# FM_TX.net
KiCad netlist of a schematic drawn in Altium Designer
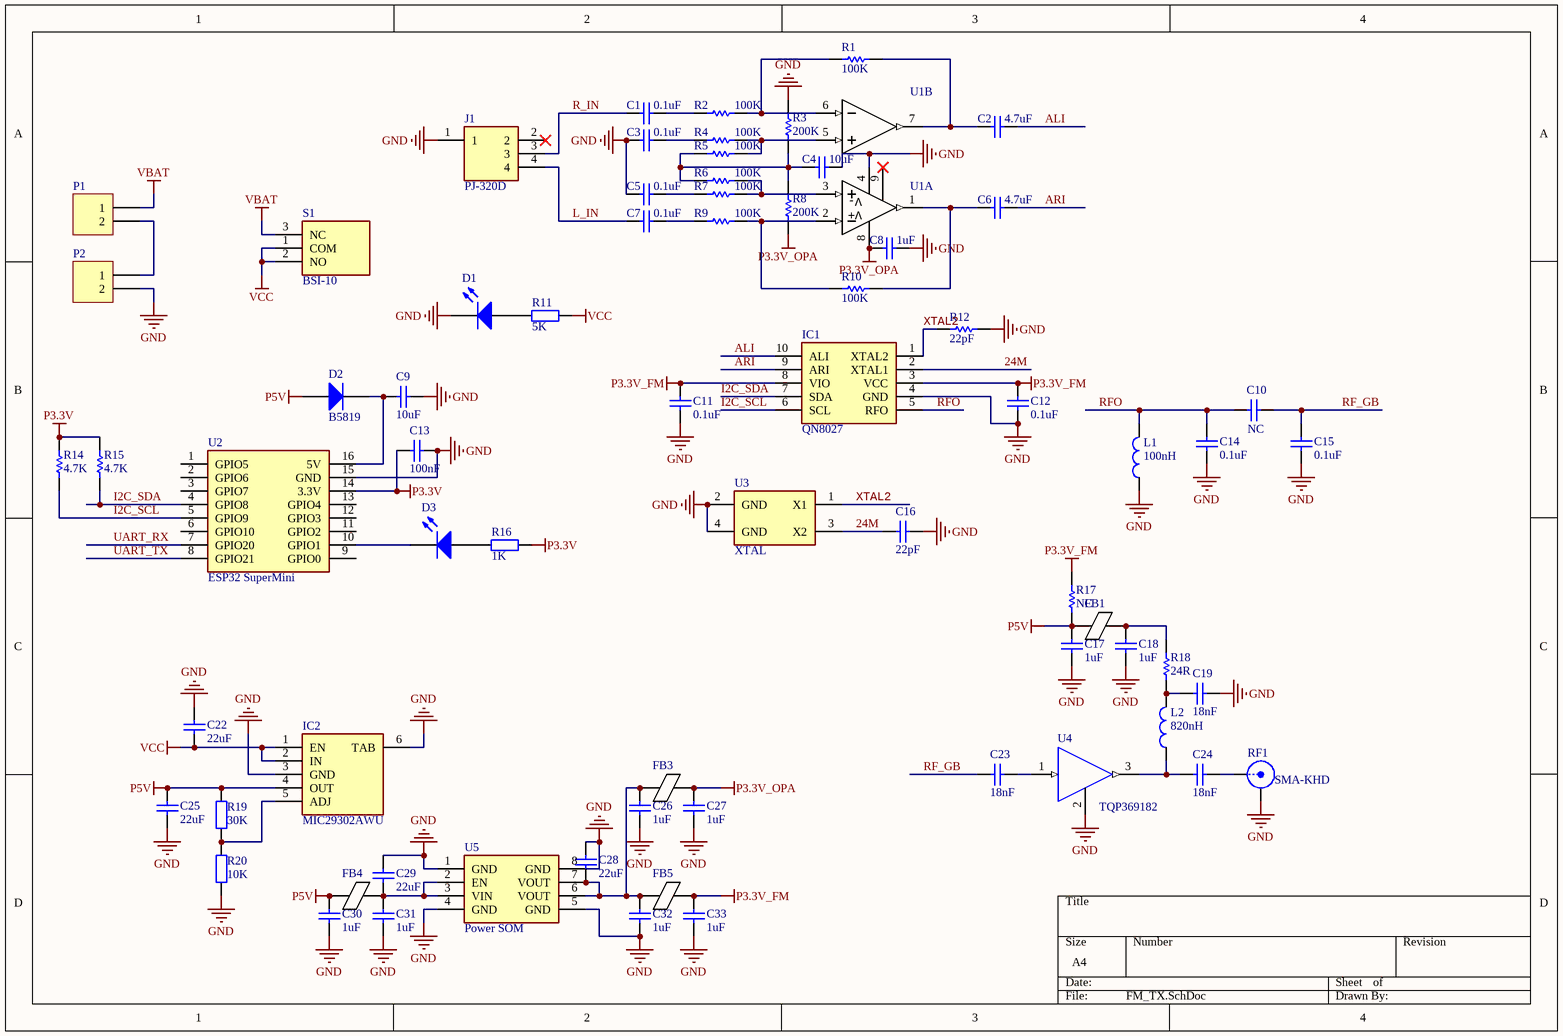
[diagram p0: FM_TX.SchDoc]

(export (version "E")
  (design (tool "Eeschema 10.0.6"))
  (components
    (comp (ref "C1")
      (value "0.1uF")
      (footprint "0603_C")
      (description "Capacitor")
      (fields (field (name "PUBLISHER") "Altium Limited"))
      (libsource (lib "My Footprint") (part "CAP"))
    )
    (comp (ref "C2")
      (value "4.7uF")
      (footprint "0603_C")
      (description "Capacitor")
      (fields (field (name "PUBLISHER") "Altium Limited"))
      (libsource (lib "My Footprint") (part "CAP"))
    )
    (comp (ref "C3")
      (value "0.1uF")
      (footprint "0603_C")
      (description "Capacitor")
      (fields (field (name "PUBLISHER") "Altium Limited"))
      (libsource (lib "My Footprint") (part "CAP"))
    )
    (comp (ref "C4")
      (value "10uF")
      (footprint "0603_C")
      (description "Capacitor")
      (fields (field (name "PUBLISHER") "Altium Limited"))
      (libsource (lib "My Footprint") (part "CAP"))
    )
    (comp (ref "C5")
      (value "0.1uF")
      (footprint "0603_C")
      (description "Capacitor")
      (fields (field (name "PUBLISHER") "Altium Limited"))
      (libsource (lib "My Footprint") (part "CAP"))
    )
    (comp (ref "C6")
      (value "4.7uF")
      (footprint "0603_C")
      (description "Capacitor")
      (fields (field (name "PUBLISHER") "Altium Limited"))
      (libsource (lib "My Footprint") (part "CAP"))
    )
    (comp (ref "C7")
      (value "0.1uF")
      (footprint "0603_C")
      (description "Capacitor")
      (fields (field (name "PUBLISHER") "Altium Limited"))
      (libsource (lib "My Footprint") (part "CAP"))
    )
    (comp (ref "C8")
      (value "1uF")
      (footprint "0603_C")
      (description "Capacitor")
      (fields (field (name "PUBLISHER") "Altium Limited"))
      (libsource (lib "My Footprint") (part "CAP"))
    )
    (comp (ref "C9")
      (value "10uF")
      (footprint "C1210")
      (description "Capacitor")
      (fields (field (name "Comment") "Cap") (field (name "PUBLISHER") "Altium Limited"))
      (libsource (lib "RegenovoPcbLib") (part "Cap"))
    )
    (comp (ref "C10")
      (value "NC")
      (footprint "0603_C")
      (description "Capacitor")
      (fields (field (name "PUBLISHER") "Altium Limited"))
      (libsource (lib "My Footprint") (part "CAP"))
    )
    (comp (ref "C11")
      (value "0.1uF")
      (footprint "0603_C")
      (description "Capacitor")
      (fields (field (name "PUBLISHER") "Altium Limited"))
      (libsource (lib "My Footprint") (part "CAP"))
    )
    (comp (ref "C12")
      (value "0.1uF")
      (footprint "0603_C")
      (description "Capacitor")
      (fields (field (name "PUBLISHER") "Altium Limited"))
      (libsource (lib "My Footprint") (part "CAP"))
    )
    (comp (ref "C13")
      (value "100nF")
      (footprint "C0603")
      (description "Capacitor")
      (fields (field (name "Comment") "Cap") (field (name "PUBLISHER") "Altium Limited"))
      (libsource (lib "RegenovoPcbLib") (part "Cap"))
    )
    (comp (ref "C14")
      (value "0.1uF")
      (footprint "0603_C")
      (description "Capacitor")
      (fields (field (name "PUBLISHER") "Altium Limited"))
      (libsource (lib "My Footprint") (part "CAP"))
    )
    (comp (ref "C15")
      (value "0.1uF")
      (footprint "0603_C")
      (description "Capacitor")
      (fields (field (name "PUBLISHER") "Altium Limited"))
      (libsource (lib "My Footprint") (part "CAP"))
    )
    (comp (ref "C16")
      (value "22pF")
      (footprint "0603_C")
      (description "Capacitor")
      (fields (field (name "PUBLISHER") "Altium Limited"))
      (libsource (lib "My Footprint") (part "CAP"))
    )
    (comp (ref "C17")
      (value "1uF")
      (footprint "0603_C")
      (description "Capacitor")
      (fields (field (name "PUBLISHER") "Altium Limited"))
      (libsource (lib "My Footprint") (part "CAP"))
    )
    (comp (ref "C18")
      (value "1uF")
      (footprint "0603_C")
      (description "Capacitor")
      (fields (field (name "PUBLISHER") "Altium Limited"))
      (libsource (lib "My Footprint") (part "CAP"))
    )
    (comp (ref "C19")
      (value "18nF")
      (footprint "0603_C")
      (description "Capacitor")
      (fields (field (name "PUBLISHER") "Altium Limited"))
      (libsource (lib "My Footprint") (part "CAP"))
    )
    (comp (ref "C22")
      (value "22uF")
      (footprint "C1210")
      (description "Capacitor")
      (fields (field (name "Comment") "Cap") (field (name "PUBLISHER") "Altium Limited"))
      (libsource (lib "RegenovoPcbLib") (part "Cap"))
    )
    (comp (ref "C23")
      (value "18nF")
      (footprint "0603_C")
      (description "Capacitor")
      (fields (field (name "PUBLISHER") "Altium Limited"))
      (libsource (lib "My Footprint") (part "CAP"))
    )
    (comp (ref "C24")
      (value "18nF")
      (footprint "0603_C")
      (description "Capacitor")
      (fields (field (name "PUBLISHER") "Altium Limited"))
      (libsource (lib "My Footprint") (part "CAP"))
    )
    (comp (ref "C25")
      (value "22uF")
      (footprint "C1210")
      (description "Capacitor")
      (fields (field (name "Comment") "Cap") (field (name "PUBLISHER") "Altium Limited"))
      (libsource (lib "RegenovoPcbLib") (part "Cap"))
    )
    (comp (ref "C26")
      (value "1uF")
      (footprint "0603_C")
      (description "Capacitor")
      (fields (field (name "PUBLISHER") "Altium Limited"))
      (libsource (lib "My Footprint") (part "CAP"))
    )
    (comp (ref "C27")
      (value "1uF")
      (footprint "0603_C")
      (description "Capacitor")
      (fields (field (name "PUBLISHER") "Altium Limited"))
      (libsource (lib "My Footprint") (part "CAP"))
    )
    (comp (ref "C28")
      (value "22uF")
      (footprint "C1210")
      (description "Capacitor")
      (fields (field (name "Comment") "Cap") (field (name "PUBLISHER") "Altium Limited"))
      (libsource (lib "RegenovoPcbLib") (part "Cap"))
    )
    (comp (ref "C29")
      (value "22uF")
      (footprint "C1210")
      (description "Capacitor")
      (fields (field (name "Comment") "Cap") (field (name "PUBLISHER") "Altium Limited"))
      (libsource (lib "RegenovoPcbLib") (part "Cap"))
    )
    (comp (ref "C30")
      (value "1uF")
      (footprint "0603_C")
      (description "Capacitor")
      (fields (field (name "PUBLISHER") "Altium Limited"))
      (libsource (lib "My Footprint") (part "CAP"))
    )
    (comp (ref "C31")
      (value "1uF")
      (footprint "0603_C")
      (description "Capacitor")
      (fields (field (name "PUBLISHER") "Altium Limited"))
      (libsource (lib "My Footprint") (part "CAP"))
    )
    (comp (ref "C32")
      (value "1uF")
      (footprint "0603_C")
      (description "Capacitor")
      (fields (field (name "PUBLISHER") "Altium Limited"))
      (libsource (lib "My Footprint") (part "CAP"))
    )
    (comp (ref "C33")
      (value "1uF")
      (footprint "0603_C")
      (description "Capacitor")
      (fields (field (name "PUBLISHER") "Altium Limited"))
      (libsource (lib "My Footprint") (part "CAP"))
    )
    (comp (ref "D1")
      (value "LED")
      (footprint "LED 0603B")
      (description "Typical RED, GREEN, YELLOW, AMBER GaAs LED")
      (fields (field (name "PUBLISHER") "Altium Limited"))
      (libsource (lib "RegenovoPcbLib") (part "LED"))
    )
    (comp (ref "D2")
      (value "B5819")
      (footprint "SOD123")
      (libsource (lib "RegenovoPcbLib") (part "Diode B5819"))
    )
    (comp (ref "D3")
      (value "LED")
      (footprint "LED 0603B")
      (description "Typical RED, GREEN, YELLOW, AMBER GaAs LED")
      (fields (field (name "PUBLISHER") "Altium Limited"))
      (libsource (lib "RegenovoPcbLib") (part "LED"))
    )
    (comp (ref "FB1")
      (value "600Ω @ 100MHz")
      (footprint "0603")
      (description "磁珠 600Ω @ 100MHz")
      (libsource (lib "My Footprint") (part "FB"))
    )
    (comp (ref "FB3")
      (value "600Ω @ 100MHz")
      (footprint "0603")
      (description "磁珠 600Ω @ 100MHz")
      (libsource (lib "My Footprint") (part "FB"))
    )
    (comp (ref "FB4")
      (value "600Ω @ 100MHz")
      (footprint "0603")
      (description "磁珠 600Ω @ 100MHz")
      (libsource (lib "My Footprint") (part "FB"))
    )
    (comp (ref "FB5")
      (value "600Ω @ 100MHz")
      (footprint "0603")
      (description "磁珠 600Ω @ 100MHz")
      (libsource (lib "My Footprint") (part "FB"))
    )
    (comp (ref "IC1")
      (value "QN8027")
      (footprint "SOP50P490X110-10N")
      (description "Integrated Circuit")
      (libsource (lib "SamacSys") (part "QN8027"))
    )
    (comp (ref "IC2")
      (value "MIC29302AWU")
      (footprint "KTT0005B")
      (description "Integrated Circuit")
      (fields (field (name "MOUSER PART NUMBER") "998-MIC29302AWU"))
      (libsource (lib "SamacSys") (part "MIC29302AWU"))
    )
    (comp (ref "J1")
      (value "PJ-320D")
      (footprint "PJ320D")
      (description "Connector")
      (libsource (lib "SamacSys") (part "PJ-320D"))
    )
    (comp (ref "L1") (value "100nH") (footprint "0805") (libsource (lib "My Footprint") (part "Inductor")))
    (comp (ref "L2") (value "820nH") (footprint "0805") (libsource (lib "My Footprint") (part "Inductor")))
    (comp (ref "P1")
      (value "Header 2")
      (footprint "XH2.54-WI-2P")
      (description "Header, 2-Pin")
      (fields (field (name "PUBLISHER") "Altium Limited"))
      (libsource (lib "RegenovoPcbLib") (part "Header 2"))
    )
    (comp (ref "P2")
      (value "Header 2")
      (footprint "XH2.54-WI-2P")
      (description "Header, 2-Pin")
      (fields (field (name "PUBLISHER") "Altium Limited"))
      (libsource (lib "RegenovoPcbLib") (part "Header 2"))
    )
    (comp (ref "R1")
      (value "100K")
      (footprint "0603_R")
      (description "Resistor")
      (fields (field (name "PUBLISHER") "Altium Limited"))
      (libsource (lib "My Footprint") (part "RES"))
    )
    (comp (ref "R2")
      (value "100K")
      (footprint "0603_R")
      (description "Resistor")
      (fields (field (name "PUBLISHER") "Altium Limited"))
      (libsource (lib "My Footprint") (part "RES"))
    )
    (comp (ref "R3")
      (value "200K")
      (footprint "0603_R")
      (description "Resistor")
      (fields (field (name "PUBLISHER") "Altium Limited"))
      (libsource (lib "My Footprint") (part "RES"))
    )
    (comp (ref "R4")
      (value "100K")
      (footprint "0603_R")
      (description "Resistor")
      (fields (field (name "PUBLISHER") "Altium Limited"))
      (libsource (lib "My Footprint") (part "RES"))
    )
    (comp (ref "R5")
      (value "100K")
      (footprint "0603_R")
      (description "Resistor")
      (fields (field (name "PUBLISHER") "Altium Limited"))
      (libsource (lib "My Footprint") (part "RES"))
    )
    (comp (ref "R6")
      (value "100K")
      (footprint "0603_R")
      (description "Resistor")
      (fields (field (name "PUBLISHER") "Altium Limited"))
      (libsource (lib "My Footprint") (part "RES"))
    )
    (comp (ref "R7")
      (value "100K")
      (footprint "0603_R")
      (description "Resistor")
      (fields (field (name "PUBLISHER") "Altium Limited"))
      (libsource (lib "My Footprint") (part "RES"))
    )
    (comp (ref "R8")
      (value "200K")
      (footprint "0603_R")
      (description "Resistor")
      (fields (field (name "PUBLISHER") "Altium Limited"))
      (libsource (lib "My Footprint") (part "RES"))
    )
    (comp (ref "R9")
      (value "100K")
      (footprint "0603_R")
      (description "Resistor")
      (fields (field (name "PUBLISHER") "Altium Limited"))
      (libsource (lib "My Footprint") (part "RES"))
    )
    (comp (ref "R10")
      (value "100K")
      (footprint "0603_R")
      (description "Resistor")
      (fields (field (name "PUBLISHER") "Altium Limited"))
      (libsource (lib "My Footprint") (part "RES"))
    )
    (comp (ref "R11")
      (value "5K")
      (footprint "R0603")
      (description "Resistor")
      (fields (field (name "Comment") "Res") (field (name "PUBLISHER") "Altium Limited"))
      (libsource (lib "") (part "Res_1"))
    )
    (comp (ref "R12")
      (value "22pF")
      (footprint "0603_R")
      (description "Resistor")
      (fields (field (name "PUBLISHER") "Altium Limited"))
      (libsource (lib "My Footprint") (part "RES"))
    )
    (comp (ref "R14")
      (value "4.7K")
      (footprint "0603_R")
      (description "Resistor")
      (fields (field (name "PUBLISHER") "Altium Limited"))
      (libsource (lib "My Footprint") (part "RES"))
    )
    (comp (ref "R15")
      (value "4.7K")
      (footprint "0603_R")
      (description "Resistor")
      (fields (field (name "PUBLISHER") "Altium Limited"))
      (libsource (lib "My Footprint") (part "RES"))
    )
    (comp (ref "R16")
      (value "1K")
      (footprint "R0603")
      (description "Resistor")
      (fields (field (name "Comment") "Res") (field (name "PUBLISHER") "Altium Limited"))
      (libsource (lib "") (part "Res_1"))
    )
    (comp (ref "R17")
      (value "NC")
      (footprint "0603_R")
      (description "Resistor")
      (fields (field (name "PUBLISHER") "Altium Limited"))
      (libsource (lib "My Footprint") (part "RES"))
    )
    (comp (ref "R18")
      (value "24R")
      (footprint "0603_R")
      (description "Resistor")
      (fields (field (name "PUBLISHER") "Altium Limited"))
      (libsource (lib "My Footprint") (part "RES"))
    )
    (comp (ref "R19")
      (value "30K")
      (footprint "R0603")
      (description "Resistor")
      (fields (field (name "Comment") "Res") (field (name "PUBLISHER") "Altium Limited"))
      (libsource (lib "RegenovoPcbLib") (part "Res"))
    )
    (comp (ref "R20")
      (value "10K")
      (footprint "R0603")
      (description "Resistor")
      (fields (field (name "Comment") "Res") (field (name "PUBLISHER") "Altium Limited"))
      (libsource (lib "RegenovoPcbLib") (part "Res"))
    )
    (comp (ref "RF1") (value "SMA-KHD") (footprint "SMA-2") (libsource (lib "My Footprint") (part "SMA_KHD")))
    (comp (ref "S1")
      (value "BSI-10")
      (footprint "BSI10")
      (description "Switch")
      (libsource (lib "SamacSys") (part "BSI-10"))
    )
    (comp (ref "U1")
      (value "OPA2211AIDRGR")
      (footprint "SOIC-8")
      (description "Imported")
      (fields
        (field (name "MANUFACTURER") "Texas Instruments")
        (field (name "GENERIC_PART_NUMBER") "OPA2365")
      )
      (libsource (lib "SamacSys") (part "OPA2211"))
    )
    (comp (ref "U2")
      (value "ESP32 SuperMini")
      (footprint "ESP32C3_MINI")
      (libsource (lib "ESP32C3") (part "ESP32 SuperMini"))
    )
    (comp (ref "U3")
      (value "XTAL")
      (footprint "OSC_KH3225_4P")
      (libsource (lib "My Footprint") (part "XTAL_SMT"))
    )
    (comp (ref "U4") (value "TQP369182") (footprint "SOT-89") (libsource (lib "My Footprint") (part "LNA")))
    (comp (ref "U5")
      (value "Power SOM")
      (footprint "7A8300")
      (libsource (lib "power_module") (part "TPS7A8300"))
    )
  )
  (nets
    (net (code "1") (name "/24M") (class "Default")
      (node (ref "C16") (pin "2") (pinfunction "2_2") (pintype "passive"))
      (node (ref "IC1") (pin "2") (pinfunction "XTAL1_2") (pintype "passive"))
      (node (ref "U3") (pin "3") (pinfunction "X2_3") (pintype "passive"))
    )
    (net (code "2") (name "/ALI") (class "Default")
      (node (ref "C2") (pin "2") (pinfunction "2_2") (pintype "passive"))
      (node (ref "IC1") (pin "10") (pinfunction "ALI_10") (pintype "passive"))
    )
    (net (code "3") (name "/ARI") (class "Default")
      (node (ref "C6") (pin "2") (pinfunction "2_2") (pintype "passive"))
      (node (ref "IC1") (pin "9") (pinfunction "ARI_9") (pintype "passive"))
    )
    (net (code "4") (name "/I2C_SCL") (class "Default")
      (node (ref "IC1") (pin "6") (pinfunction "SCL_6") (pintype "passive"))
      (node (ref "R14") (pin "1") (pinfunction "1_1") (pintype "passive"))
      (node (ref "U2") (pin "5") (pinfunction "GPIO9_5") (pintype "passive"))
    )
    (net (code "5") (name "/I2C_SDA") (class "Default")
      (node (ref "IC1") (pin "7") (pinfunction "SDA_7") (pintype "passive"))
      (node (ref "R15") (pin "1") (pinfunction "1_1") (pintype "passive"))
      (node (ref "U2") (pin "4") (pinfunction "GPIO8_4") (pintype "passive"))
    )
    (net (code "6") (name "/L_IN") (class "Default")
      (node (ref "C7") (pin "1") (pinfunction "1_1") (pintype "passive"))
      (node (ref "J1") (pin "4") (pinfunction "4_4") (pintype "passive"))
    )
    (net (code "7") (name "/RFO") (class "Default")
      (node (ref "C10") (pin "2") (pinfunction "2_2") (pintype "passive"))
      (node (ref "C14") (pin "2") (pinfunction "2_2") (pintype "passive"))
      (node (ref "IC1") (pin "5") (pinfunction "RFO_5") (pintype "passive"))
      (node (ref "L1") (pin "2") (pinfunction "2_2") (pintype "passive"))
    )
    (net (code "8") (name "/RF_GB") (class "Default")
      (node (ref "C10") (pin "1") (pinfunction "1_1") (pintype "passive"))
      (node (ref "C15") (pin "2") (pinfunction "2_2") (pintype "passive"))
      (node (ref "C23") (pin "1") (pinfunction "1_1") (pintype "passive"))
    )
    (net (code "9") (name "/R_IN") (class "Default")
      (node (ref "C1") (pin "1") (pinfunction "1_1") (pintype "passive"))
      (node (ref "J1") (pin "3") (pinfunction "3_3") (pintype "passive"))
    )
    (net (code "10") (name "/UART_RX") (class "Default")
      (node (ref "U2") (pin "7") (pinfunction "GPIO20_7") (pintype "passive"))
    )
    (net (code "11") (name "/UART_TX") (class "Default")
      (node (ref "U2") (pin "8") (pinfunction "GPIO21_8") (pintype "passive"))
    )
    (net (code "12") (name "/XTAL2") (class "Default")
      (node (ref "IC1") (pin "1") (pinfunction "XTAL2_1") (pintype "passive"))
      (node (ref "R12") (pin "1") (pinfunction "1_1") (pintype "passive"))
      (node (ref "U3") (pin "1") (pinfunction "X1_1") (pintype "passive"))
    )
    (net (code "13") (name "GND") (class "Default")
      (node (ref "C11") (pin "1") (pinfunction "1_1") (pintype "passive"))
      (node (ref "C12") (pin "1") (pinfunction "1_1") (pintype "passive"))
      (node (ref "C13") (pin "2") (pinfunction "2_2") (pintype "passive"))
      (node (ref "C14") (pin "1") (pinfunction "1_1") (pintype "passive"))
      (node (ref "C15") (pin "1") (pinfunction "1_1") (pintype "passive"))
      (node (ref "C16") (pin "1") (pinfunction "1_1") (pintype "passive"))
      (node (ref "C17") (pin "1") (pinfunction "1_1") (pintype "passive"))
      (node (ref "C18") (pin "1") (pinfunction "1_1") (pintype "passive"))
      (node (ref "C19") (pin "2") (pinfunction "2_2") (pintype "passive"))
      (node (ref "C22") (pin "1") (pinfunction "1_1") (pintype "passive"))
      (node (ref "C25") (pin "1") (pinfunction "1_1") (pintype "passive"))
      (node (ref "C26") (pin "1") (pinfunction "1_1") (pintype "passive"))
      (node (ref "C27") (pin "1") (pinfunction "1_1") (pintype "passive"))
      (node (ref "C28") (pin "1") (pinfunction "1_1") (pintype "passive"))
      (node (ref "C29") (pin "2") (pinfunction "2_2") (pintype "passive"))
      (node (ref "C3") (pin "1") (pinfunction "1_1") (pintype "passive"))
      (node (ref "C30") (pin "1") (pinfunction "1_1") (pintype "passive"))
      (node (ref "C31") (pin "1") (pinfunction "1_1") (pintype "passive"))
      (node (ref "C32") (pin "1") (pinfunction "1_1") (pintype "passive"))
      (node (ref "C33") (pin "1") (pinfunction "1_1") (pintype "passive"))
      (node (ref "C4") (pin "2") (pinfunction "2_2") (pintype "passive"))
      (node (ref "C5") (pin "1") (pinfunction "1_1") (pintype "passive"))
      (node (ref "C8") (pin "2") (pinfunction "2_2") (pintype "passive"))
      (node (ref "C9") (pin "1") (pinfunction "1_1") (pintype "passive"))
      (node (ref "D1") (pin "2") (pinfunction "K_2") (pintype "passive"))
      (node (ref "IC1") (pin "4") (pinfunction "GND_4") (pintype "passive"))
      (node (ref "IC2") (pin "3") (pinfunction "GND_3") (pintype "passive"))
      (node (ref "IC2") (pin "6") (pinfunction "TAB_6") (pintype "passive"))
      (node (ref "J1") (pin "1") (pinfunction "1_1") (pintype "passive"))
      (node (ref "L1") (pin "1") (pinfunction "1_1") (pintype "passive"))
      (node (ref "P2") (pin "2") (pinfunction "2_2") (pintype "passive"))
      (node (ref "R12") (pin "2") (pinfunction "2_2") (pintype "passive"))
      (node (ref "R20") (pin "1") (pinfunction "1_1") (pintype "passive"))
      (node (ref "R3") (pin "1") (pinfunction "1_1") (pintype "passive"))
      (node (ref "RF1") (pin "2") (pinfunction "2_2") (pintype "passive"))
      (node (ref "U1") (pin "4") (pinfunction "V-_4") (pintype "power_in"))
      (node (ref "U2") (pin "15") (pinfunction "GND_15") (pintype "passive"))
      (node (ref "U3") (pin "2") (pinfunction "GND_2") (pintype "passive"))
      (node (ref "U3") (pin "4") (pinfunction "GND_4") (pintype "passive"))
      (node (ref "U4") (pin "2") (pinfunction "V-_2") (pintype "power_in"))
      (node (ref "U5") (pin "1") (pinfunction "GND_1") (pintype "passive"))
      (node (ref "U5") (pin "4") (pinfunction "GND_4") (pintype "passive"))
      (node (ref "U5") (pin "5") (pinfunction "GND_5") (pintype "passive"))
      (node (ref "U5") (pin "8") (pinfunction "GND_8") (pintype "passive"))
    )
    (net (code "14") (name "Net-(C1-Pad2)") (class "Default")
      (node (ref "C1") (pin "2") (pinfunction "2_2") (pintype "passive"))
      (node (ref "R2") (pin "1") (pinfunction "1_1") (pintype "passive"))
    )
    (net (code "15") (name "Net-(C3-Pad2)") (class "Default")
      (node (ref "C3") (pin "2") (pinfunction "2_2") (pintype "passive"))
      (node (ref "R4") (pin "1") (pinfunction "1_1") (pintype "passive"))
    )
    (net (code "16") (name "Net-(C4-Pad1)") (class "Default")
      (node (ref "C4") (pin "1") (pinfunction "1_1") (pintype "passive"))
      (node (ref "R3") (pin "2") (pinfunction "2_2") (pintype "passive"))
      (node (ref "R5") (pin "1") (pinfunction "1_1") (pintype "passive"))
      (node (ref "R6") (pin "1") (pinfunction "1_1") (pintype "passive"))
      (node (ref "R8") (pin "2") (pinfunction "2_2") (pintype "passive"))
    )
    (net (code "17") (name "Net-(C5-Pad2)") (class "Default")
      (node (ref "C5") (pin "2") (pinfunction "2_2") (pintype "passive"))
      (node (ref "R7") (pin "1") (pinfunction "1_1") (pintype "passive"))
    )
    (net (code "18") (name "Net-(C7-Pad2)") (class "Default")
      (node (ref "C7") (pin "2") (pinfunction "2_2") (pintype "passive"))
      (node (ref "R9") (pin "1") (pinfunction "1_1") (pintype "passive"))
    )
    (net (code "19") (name "Net-(C18-Pad2)") (class "Default")
      (node (ref "C18") (pin "2") (pinfunction "2_2") (pintype "passive"))
      (node (ref "FB1") (pin "2") (pinfunction "2_2") (pintype "passive"))
      (node (ref "R18") (pin "2") (pinfunction "2_2") (pintype "passive"))
    )
    (net (code "20") (name "Net-(C19-Pad1)") (class "Default")
      (node (ref "C19") (pin "1") (pinfunction "1_1") (pintype "passive"))
      (node (ref "L2") (pin "2") (pinfunction "2_2") (pintype "passive"))
      (node (ref "R18") (pin "1") (pinfunction "1_1") (pintype "passive"))
    )
    (net (code "21") (name "Net-(C24-Pad2)") (class "Default")
      (node (ref "C24") (pin "2") (pinfunction "2_2") (pintype "passive"))
      (node (ref "RF1") (pin "1") (pinfunction "1_1") (pintype "passive"))
    )
    (net (code "22") (name "Net-(C26-Pad2)") (class "Default")
      (node (ref "C26") (pin "2") (pinfunction "2_2") (pintype "passive"))
      (node (ref "C28") (pin "2") (pinfunction "2_2") (pintype "passive"))
      (node (ref "C32") (pin "2") (pinfunction "2_2") (pintype "passive"))
      (node (ref "FB3") (pin "1") (pinfunction "1_1") (pintype "passive"))
      (node (ref "FB5") (pin "1") (pinfunction "1_1") (pintype "passive"))
      (node (ref "U5") (pin "6") (pinfunction "VOUT_6") (pintype "passive"))
      (node (ref "U5") (pin "7") (pinfunction "VOUT_7") (pintype "passive"))
    )
    (net (code "23") (name "Net-(D1-A)") (class "Default")
      (node (ref "D1") (pin "1") (pinfunction "A_1") (pintype "passive"))
      (node (ref "R11") (pin "1") (pinfunction "1_1") (pintype "passive"))
    )
    (net (code "24") (name "Net-(D2-K)") (class "Default")
      (node (ref "C9") (pin "2") (pinfunction "2_2") (pintype "passive"))
      (node (ref "D2") (pin "2") (pinfunction "K_2") (pintype "passive"))
      (node (ref "U2") (pin "16") (pinfunction "5V_16") (pintype "passive"))
    )
    (net (code "25") (name "Net-(D3-A)") (class "Default")
      (node (ref "D3") (pin "1") (pinfunction "A_1") (pintype "passive"))
      (node (ref "R16") (pin "1") (pinfunction "1_1") (pintype "passive"))
    )
    (net (code "26") (name "Net-(D3-K)") (class "Default")
      (node (ref "D3") (pin "2") (pinfunction "K_2") (pintype "passive"))
      (node (ref "U2") (pin "10") (pinfunction "GPIO1_10") (pintype "passive"))
    )
    (net (code "27") (name "Net-(IC2-ADJ)") (class "Default")
      (node (ref "IC2") (pin "5") (pinfunction "ADJ_5") (pintype "passive"))
      (node (ref "R19") (pin "1") (pinfunction "1_1") (pintype "passive"))
      (node (ref "R20") (pin "2") (pinfunction "2_2") (pintype "passive"))
    )
    (net (code "28") (name "Net-(P1-Pad2)") (class "Default")
      (node (ref "P1") (pin "2") (pinfunction "2_2") (pintype "passive"))
      (node (ref "P2") (pin "1") (pinfunction "1_1") (pintype "passive"))
    )
    (net (code "29") (name "Net-(U1A-1IN+)") (class "Default")
      (node (ref "R6") (pin "2") (pinfunction "2_2") (pintype "passive"))
      (node (ref "R7") (pin "2") (pinfunction "2_2") (pintype "passive"))
      (node (ref "U1") (pin "3") (pinfunction "1IN+_3") (pintype "input"))
    )
    (net (code "30") (name "Net-(U1A-1IN-)") (class "Default")
      (node (ref "R10") (pin "1") (pinfunction "1_1") (pintype "passive"))
      (node (ref "R9") (pin "2") (pinfunction "2_2") (pintype "passive"))
      (node (ref "U1") (pin "2") (pinfunction "1IN-_2") (pintype "input"))
    )
    (net (code "31") (name "Net-(U1A-1OUT)") (class "Default")
      (node (ref "C6") (pin "1") (pinfunction "1_1") (pintype "passive"))
      (node (ref "R10") (pin "2") (pinfunction "2_2") (pintype "passive"))
      (node (ref "U1") (pin "1") (pinfunction "1OUT_1") (pintype "output"))
    )
    (net (code "32") (name "Net-(U1B-2IN+)") (class "Default")
      (node (ref "R4") (pin "2") (pinfunction "2_2") (pintype "passive"))
      (node (ref "R5") (pin "2") (pinfunction "2_2") (pintype "passive"))
      (node (ref "U1") (pin "5") (pinfunction "2IN+_5") (pintype "input"))
    )
    (net (code "33") (name "Net-(U1B-2IN-)") (class "Default")
      (node (ref "R1") (pin "1") (pinfunction "1_1") (pintype "passive"))
      (node (ref "R2") (pin "2") (pinfunction "2_2") (pintype "passive"))
      (node (ref "U1") (pin "6") (pinfunction "2IN-_6") (pintype "input"))
    )
    (net (code "34") (name "Net-(U1B-2OUT)") (class "Default")
      (node (ref "C2") (pin "1") (pinfunction "1_1") (pintype "passive"))
      (node (ref "R1") (pin "2") (pinfunction "2_2") (pintype "passive"))
      (node (ref "U1") (pin "7") (pinfunction "2OUT_7") (pintype "output"))
    )
    (net (code "35") (name "Net-(U4-IN+)") (class "Default")
      (node (ref "C23") (pin "2") (pinfunction "2_2") (pintype "passive"))
      (node (ref "U4") (pin "1") (pinfunction "IN+_1") (pintype "input"))
    )
    (net (code "36") (name "Net-(U4-OUT)") (class "Default")
      (node (ref "C24") (pin "1") (pinfunction "1_1") (pintype "passive"))
      (node (ref "L2") (pin "1") (pinfunction "1_1") (pintype "passive"))
      (node (ref "U4") (pin "3") (pinfunction "OUT_3") (pintype "output"))
    )
    (net (code "37") (name "Net-(U5-EN)") (class "Default")
      (node (ref "C29") (pin "1") (pinfunction "1_1") (pintype "passive"))
      (node (ref "C31") (pin "2") (pinfunction "2_2") (pintype "passive"))
      (node (ref "FB4") (pin "2") (pinfunction "2_2") (pintype "passive"))
      (node (ref "U5") (pin "2") (pinfunction "EN_2") (pintype "passive"))
      (node (ref "U5") (pin "3") (pinfunction "VIN_3") (pintype "passive"))
    )
    (net (code "38") (name "P3.3V") (class "Default")
      (node (ref "C13") (pin "1") (pinfunction "1_1") (pintype "passive"))
      (node (ref "R14") (pin "2") (pinfunction "2_2") (pintype "passive"))
      (node (ref "R15") (pin "2") (pinfunction "2_2") (pintype "passive"))
      (node (ref "R16") (pin "2") (pinfunction "2_2") (pintype "passive"))
      (node (ref "U2") (pin "14") (pinfunction "3.3V_14") (pintype "passive"))
    )
    (net (code "39") (name "P3.3V_FM") (class "Default")
      (node (ref "C11") (pin "2") (pinfunction "2_2") (pintype "passive"))
      (node (ref "C12") (pin "2") (pinfunction "2_2") (pintype "passive"))
      (node (ref "C33") (pin "2") (pinfunction "2_2") (pintype "passive"))
      (node (ref "FB5") (pin "2") (pinfunction "2_2") (pintype "passive"))
      (node (ref "IC1") (pin "3") (pinfunction "VCC_3") (pintype "passive"))
      (node (ref "IC1") (pin "8") (pinfunction "VIO_8") (pintype "passive"))
      (node (ref "R17") (pin "2") (pinfunction "2_2") (pintype "passive"))
    )
    (net (code "40") (name "P3.3V_OPA") (class "Default")
      (node (ref "C27") (pin "2") (pinfunction "2_2") (pintype "passive"))
      (node (ref "C8") (pin "1") (pinfunction "1_1") (pintype "passive"))
      (node (ref "FB3") (pin "2") (pinfunction "2_2") (pintype "passive"))
      (node (ref "R8") (pin "1") (pinfunction "1_1") (pintype "passive"))
      (node (ref "U1") (pin "8") (pinfunction "V+_8") (pintype "power_in"))
    )
    (net (code "41") (name "P5V") (class "Default")
      (node (ref "C17") (pin "2") (pinfunction "2_2") (pintype "passive"))
      (node (ref "C25") (pin "2") (pinfunction "2_2") (pintype "passive"))
      (node (ref "C30") (pin "2") (pinfunction "2_2") (pintype "passive"))
      (node (ref "D2") (pin "1") (pinfunction "A_1") (pintype "passive"))
      (node (ref "FB1") (pin "1") (pinfunction "1_1") (pintype "passive"))
      (node (ref "FB4") (pin "1") (pinfunction "1_1") (pintype "passive"))
      (node (ref "IC2") (pin "4") (pinfunction "OUT_4") (pintype "passive"))
      (node (ref "R17") (pin "1") (pinfunction "1_1") (pintype "passive"))
      (node (ref "R19") (pin "2") (pinfunction "2_2") (pintype "passive"))
    )
    (net (code "42") (name "VBAT") (class "Default")
      (node (ref "P1") (pin "1") (pinfunction "1_1") (pintype "passive"))
      (node (ref "S1") (pin "3") (pinfunction "NC_3") (pintype "passive"))
    )
    (net (code "43") (name "VCC") (class "Default")
      (node (ref "C22") (pin "2") (pinfunction "2_2") (pintype "passive"))
      (node (ref "IC2") (pin "1") (pinfunction "EN_1") (pintype "passive"))
      (node (ref "IC2") (pin "2") (pinfunction "IN_2") (pintype "passive"))
      (node (ref "R11") (pin "2") (pinfunction "2_2") (pintype "passive"))
      (node (ref "S1") (pin "1") (pinfunction "COM_1") (pintype "passive"))
      (node (ref "S1") (pin "2") (pinfunction "NO_2") (pintype "passive"))
    )
    (net (code "44") (name "unconnected-(J1-Pad2)") (class "Default")
      (node (ref "J1") (pin "2") (pinfunction "2_2") (pintype "passive+no_connect"))
    )
    (net (code "45") (name "unconnected-(U1-Pad9)") (class "Default")
      (node (ref "U1") (pin "9") (pinfunction "9_9") (pintype "passive+no_connect"))
    )
    (net (code "46") (name "unconnected-(U2-GPIO0-Pad9)") (class "Default")
      (node (ref "U2") (pin "9") (pinfunction "GPIO0_9") (pintype "passive"))
    )
    (net (code "47") (name "unconnected-(U2-GPIO2-Pad11)") (class "Default")
      (node (ref "U2") (pin "11") (pinfunction "GPIO2_11") (pintype "passive"))
    )
    (net (code "48") (name "unconnected-(U2-GPIO3-Pad12)") (class "Default")
      (node (ref "U2") (pin "12") (pinfunction "GPIO3_12") (pintype "passive"))
    )
    (net (code "49") (name "unconnected-(U2-GPIO4-Pad13)") (class "Default")
      (node (ref "U2") (pin "13") (pinfunction "GPIO4_13") (pintype "passive"))
    )
    (net (code "50") (name "unconnected-(U2-GPIO5-Pad1)") (class "Default")
      (node (ref "U2") (pin "1") (pinfunction "GPIO5_1") (pintype "passive"))
    )
    (net (code "51") (name "unconnected-(U2-GPIO6-Pad2)") (class "Default")
      (node (ref "U2") (pin "2") (pinfunction "GPIO6_2") (pintype "passive"))
    )
    (net (code "52") (name "unconnected-(U2-GPIO7-Pad3)") (class "Default")
      (node (ref "U2") (pin "3") (pinfunction "GPIO7_3") (pintype "passive"))
    )
    (net (code "53") (name "unconnected-(U2-GPIO10-Pad6)") (class "Default")
      (node (ref "U2") (pin "6") (pinfunction "GPIO10_6") (pintype "passive"))
    )
  )
)
